# RTD_100R_With_Comp.net
KiCad netlist of a schematic drawn in Altium Designer
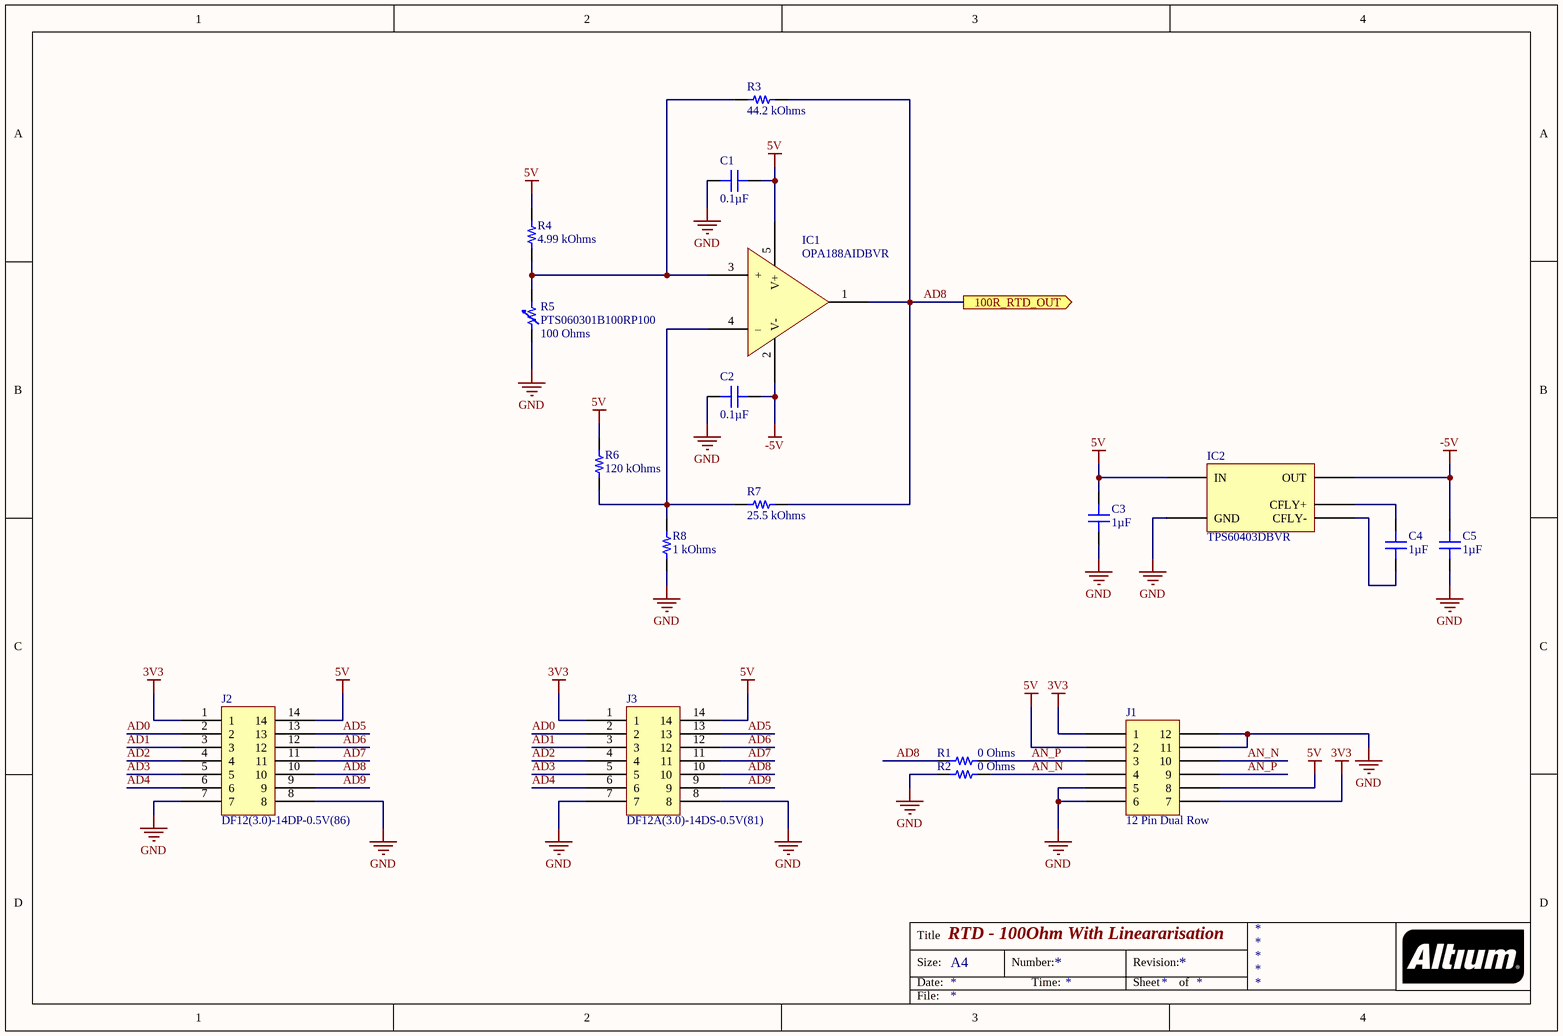
[diagram p0: RTD 100R With Comp.SchDoc]

(export (version "E")
  (design (tool "Eeschema 10.0.6"))
  (components
    (comp (ref "C1")
      (value "0.1µF")
      (footprint "CAP 0603_1608")
      (description "CAP CER 0.1UF 16V Y5V 0603")
      (fields (field (name "PART NUMBER") "CC0603ZRY5V7BB104") (field (name "MANUFACTURER") "Yageo"))
      (libsource (lib "altiumlibrary.com") (part "Capacitor"))
    )
    (comp (ref "C2")
      (value "0.1µF")
      (footprint "CAP 0603_1608")
      (description "CAP CER 0.1UF 16V Y5V 0603")
      (fields (field (name "PART NUMBER") "CC0603ZRY5V7BB104") (field (name "MANUFACTURER") "Yageo"))
      (libsource (lib "altiumlibrary.com") (part "Capacitor"))
    )
    (comp (ref "C3")
      (value "1µF")
      (footprint "CAP 0603_1608")
      (description "CAP CER 1UF 25V X7R 0603")
      (fields
        (field (name "PART NUMBER") "CL10B105KA8NNNC")
        (field (name "MANUFACTURER") "Samsung Electro-Mechanics")
      )
      (libsource (lib "altiumlibrary.com") (part "Capacitor"))
    )
    (comp (ref "C4")
      (value "1µF")
      (footprint "CAP 0603_1608")
      (description "CAP CER 1UF 25V X7R 0603")
      (fields
        (field (name "PART NUMBER") "CL10B105KA8NNNC")
        (field (name "MANUFACTURER") "Samsung Electro-Mechanics")
      )
      (libsource (lib "altiumlibrary.com") (part "Capacitor"))
    )
    (comp (ref "C5")
      (value "1µF")
      (footprint "CAP 0603_1608")
      (description "CAP CER 1UF 25V X7R 0603")
      (fields
        (field (name "PART NUMBER") "CL10B105KA8NNNC")
        (field (name "MANUFACTURER") "Samsung Electro-Mechanics")
      )
      (libsource (lib "altiumlibrary.com") (part "Capacitor"))
    )
    (comp (ref "IC1")
      (value "OPA188AIDBVR")
      (footprint "TI SOT-23-5 DBV")
      (description "IC OPAMP ZER-DRIFT 1CIRC SOT23-5")
      (fields (field (name "MANUFACTURER") "Texas Instruments"))
      (libsource (lib "altiumlibrary.com") (part "TI OPA188 DBV"))
    )
    (comp (ref "IC2")
      (value "TPS60403DBVR")
      (footprint "TI SOT-23-5 DBV")
      (description "IC REG CHARG PUMP INV 60MA SOT23")
      (fields (field (name "MANUFACTURER") "Texas Instruments"))
      (libsource (lib "altiumlibrary.com") (part "TI TPS60403"))
    )
    (comp (ref "J1")
      (value "12 Pin Dual Row")
      (footprint "TE 5650118-3 Card Edge")
      (libsource (lib "CelestialUseful") (part "12 Pin Dual Row"))
    )
    (comp (ref "J2")
      (value "DF12(3.0)-14DP-0.5V(86)")
      (footprint "HIROSE DF12 3.0-14DP-0.5V 86")
      (description "CONN HDR 14POS SMD GOLD")
      (fields (field (name "MANUFACTURER") "Hirose Electric Co Ltd"))
      (libsource (lib "altiumlibrary.com") (part "14 Pin Dual Row"))
    )
    (comp (ref "J3")
      (value "DF12A(3.0)-14DS-0.5V(81)")
      (footprint "HIROSE DF12A 3.0-14DS-0.5V 81")
      (description "CONN RCPT 14POS SMD GOLD")
      (fields (field (name "MANUFACTURER") "Hirose Electric Co Ltd"))
      (libsource (lib "altiumlibrary.com") (part "14 Pin Dual Row"))
    )
    (comp (ref "R1")
      (value "0 Ohms")
      (footprint "RES 0603_1608")
      (description "RES SMD 0 OHM JUMPER 1/10W 0603")
      (fields
        (field (name "PART NUMBER") "ERJ-3GEY0R00V")
        (field (name "MANUFACTURER") "Panasonic Electronic Components")
      )
      (libsource (lib "altiumlibrary.com") (part "Resistor"))
    )
    (comp (ref "R2")
      (value "0 Ohms")
      (footprint "RES 0603_1608")
      (description "RES SMD 0 OHM JUMPER 1/10W 0603")
      (fields
        (field (name "PART NUMBER") "ERJ-3GEY0R00V")
        (field (name "MANUFACTURER") "Panasonic Electronic Components")
      )
      (libsource (lib "altiumlibrary.com") (part "Resistor"))
    )
    (comp (ref "R3")
      (value "44.2 kOhms")
      (footprint "RES 0603_1608")
      (description "RES SMD 44.2K OHM 1% 1/10W 0603")
      (fields
        (field (name "PART NUMBER") "ERJ-3EKF4422V")
        (field (name "MANUFACTURER") "Panasonic Electronic Components")
      )
      (libsource (lib "altiumlibrary.com") (part "Resistor"))
    )
    (comp (ref "R4")
      (value "4.99 kOhms")
      (footprint "RES 0603_1608")
      (description "RES SMD 4.99K OHM 1% 1/10W 0603")
      (fields
        (field (name "PART NUMBER") "ERJ-3EKF4991V")
        (field (name "MANUFACTURER") "Panasonic Electronic Components")
      )
      (libsource (lib "altiumlibrary.com") (part "Resistor"))
    )
    (comp (ref "R5")
      (value "PTS060301B100RP100")
      (footprint "RTD 0603_1608")
      (description "SENSOR RTD 100OHM 1% 0603")
      (fields (field (name "MANUFACTURER") "Vishay Beyschlag") (field (name "RESISTANCE @ 0°C") "100 Ohms"))
      (libsource (lib "altiumlibrary.com") (part "RTD"))
    )
    (comp (ref "R6")
      (value "120 kOhms")
      (footprint "RES 0603_1608")
      (description "RES SMD 120K OHM 1% 1/10W 0603")
      (fields
        (field (name "PART NUMBER") "ERJ-3EKF1203V")
        (field (name "MANUFACTURER") "Panasonic Electronic Components")
      )
      (libsource (lib "altiumlibrary.com") (part "Resistor"))
    )
    (comp (ref "R7")
      (value "25.5 kOhms")
      (footprint "RES 0603_1608")
      (description "RES SMD 25.5K OHM 1% 1/10W 0603")
      (fields
        (field (name "PART NUMBER") "ERJ-3EKF2552V")
        (field (name "MANUFACTURER") "Panasonic Electronic Components")
      )
      (libsource (lib "altiumlibrary.com") (part "Resistor"))
    )
    (comp (ref "R8")
      (value "1 kOhms")
      (footprint "RES 0603_1608")
      (description "RES SMD 1K OHM 1% 1/10W 0603")
      (fields
        (field (name "PART NUMBER") "ERJ-3EKF1001V")
        (field (name "MANUFACTURER") "Panasonic Electronic Components")
      )
      (libsource (lib "altiumlibrary.com") (part "Resistor"))
    )
  )
  (nets
    (net (code "1") (name "-5V") (class "Default")
      (node (ref "C2") (pin "2") (pinfunction "2_2") (pintype "passive"))
      (node (ref "C5") (pin "2") (pinfunction "2_2") (pintype "passive"))
      (node (ref "IC1") (pin "2") (pinfunction "V-_2") (pintype "passive"))
      (node (ref "IC2") (pin "1") (pinfunction "OUT_1") (pintype "passive"))
    )
    (net (code "2") (name "/AD0") (class "Default")
      (node (ref "J2") (pin "2") (pinfunction "2_2") (pintype "passive"))
      (node (ref "J3") (pin "2") (pinfunction "2_2") (pintype "passive"))
    )
    (net (code "3") (name "/AD1") (class "Default")
      (node (ref "J2") (pin "3") (pinfunction "3_3") (pintype "passive"))
      (node (ref "J3") (pin "3") (pinfunction "3_3") (pintype "passive"))
    )
    (net (code "4") (name "/AD2") (class "Default")
      (node (ref "J2") (pin "4") (pinfunction "4_4") (pintype "passive"))
      (node (ref "J3") (pin "4") (pinfunction "4_4") (pintype "passive"))
    )
    (net (code "5") (name "/AD3") (class "Default")
      (node (ref "J2") (pin "5") (pinfunction "5_5") (pintype "passive"))
      (node (ref "J3") (pin "5") (pinfunction "5_5") (pintype "passive"))
    )
    (net (code "6") (name "/AD4") (class "Default")
      (node (ref "J2") (pin "6") (pinfunction "6_6") (pintype "passive"))
      (node (ref "J3") (pin "6") (pinfunction "6_6") (pintype "passive"))
    )
    (net (code "7") (name "/AD5") (class "Default")
      (node (ref "J2") (pin "13") (pinfunction "13_13") (pintype "passive"))
      (node (ref "J3") (pin "13") (pinfunction "13_13") (pintype "passive"))
    )
    (net (code "8") (name "/AD6") (class "Default")
      (node (ref "J2") (pin "12") (pinfunction "12_12") (pintype "passive"))
      (node (ref "J3") (pin "12") (pinfunction "12_12") (pintype "passive"))
    )
    (net (code "9") (name "/AD7") (class "Default")
      (node (ref "J2") (pin "11") (pinfunction "11_11") (pintype "passive"))
      (node (ref "J3") (pin "11") (pinfunction "11_11") (pintype "passive"))
    )
    (net (code "10") (name "/AD8") (class "Default")
      (node (ref "IC1") (pin "1") (pinfunction "OUT_1") (pintype "passive"))
      (node (ref "J2") (pin "10") (pinfunction "10_10") (pintype "passive"))
      (node (ref "J3") (pin "10") (pinfunction "10_10") (pintype "passive"))
      (node (ref "R1") (pin "1") (pinfunction "1_1") (pintype "passive"))
      (node (ref "R3") (pin "2") (pinfunction "2_2") (pintype "passive"))
      (node (ref "R7") (pin "2") (pinfunction "2_2") (pintype "passive"))
    )
    (net (code "11") (name "/AD9") (class "Default")
      (node (ref "J2") (pin "9") (pinfunction "9_9") (pintype "passive"))
      (node (ref "J3") (pin "9") (pinfunction "9_9") (pintype "passive"))
    )
    (net (code "12") (name "/AN_N") (class "Default")
      (node (ref "J1") (pin "10") (pinfunction "10_10") (pintype "passive"))
      (node (ref "J1") (pin "4") (pinfunction "4_4") (pintype "passive"))
      (node (ref "R2") (pin "2") (pinfunction "2_2") (pintype "passive"))
    )
    (net (code "13") (name "/AN_P") (class "Default")
      (node (ref "J1") (pin "3") (pinfunction "3_3") (pintype "passive"))
      (node (ref "J1") (pin "9") (pinfunction "9_9") (pintype "passive"))
      (node (ref "R1") (pin "2") (pinfunction "2_2") (pintype "passive"))
    )
    (net (code "14") (name "3V3") (class "Default")
      (node (ref "J1") (pin "1") (pinfunction "1_1") (pintype "passive"))
      (node (ref "J1") (pin "7") (pinfunction "7_7") (pintype "passive"))
      (node (ref "J2") (pin "1") (pinfunction "1_1") (pintype "passive"))
      (node (ref "J3") (pin "1") (pinfunction "1_1") (pintype "passive"))
    )
    (net (code "15") (name "5V") (class "Default")
      (node (ref "C1") (pin "2") (pinfunction "2_2") (pintype "passive"))
      (node (ref "C3") (pin "2") (pinfunction "2_2") (pintype "passive"))
      (node (ref "IC1") (pin "5") (pinfunction "V+_5") (pintype "passive"))
      (node (ref "IC2") (pin "2") (pinfunction "IN_2") (pintype "passive"))
      (node (ref "J1") (pin "2") (pinfunction "2_2") (pintype "passive"))
      (node (ref "J1") (pin "8") (pinfunction "8_8") (pintype "passive"))
      (node (ref "J2") (pin "14") (pinfunction "14_14") (pintype "passive"))
      (node (ref "J3") (pin "14") (pinfunction "14_14") (pintype "passive"))
      (node (ref "R4") (pin "2") (pinfunction "2_2") (pintype "passive"))
      (node (ref "R6") (pin "2") (pinfunction "2_2") (pintype "passive"))
    )
    (net (code "16") (name "GND") (class "Default")
      (node (ref "C1") (pin "1") (pinfunction "1_1") (pintype "passive"))
      (node (ref "C2") (pin "1") (pinfunction "1_1") (pintype "passive"))
      (node (ref "C3") (pin "1") (pinfunction "1_1") (pintype "passive"))
      (node (ref "C5") (pin "1") (pinfunction "1_1") (pintype "passive"))
      (node (ref "IC2") (pin "4") (pinfunction "GND_4") (pintype "passive"))
      (node (ref "J1") (pin "11") (pinfunction "11_11") (pintype "passive"))
      (node (ref "J1") (pin "12") (pinfunction "12_12") (pintype "passive"))
      (node (ref "J1") (pin "5") (pinfunction "5_5") (pintype "passive"))
      (node (ref "J1") (pin "6") (pinfunction "6_6") (pintype "passive"))
      (node (ref "J2") (pin "7") (pinfunction "7_7") (pintype "passive"))
      (node (ref "J2") (pin "8") (pinfunction "8_8") (pintype "passive"))
      (node (ref "J3") (pin "7") (pinfunction "7_7") (pintype "passive"))
      (node (ref "J3") (pin "8") (pinfunction "8_8") (pintype "passive"))
      (node (ref "R2") (pin "1") (pinfunction "1_1") (pintype "passive"))
      (node (ref "R5") (pin "1") (pinfunction "1_1") (pintype "passive"))
      (node (ref "R8") (pin "1") (pinfunction "1_1") (pintype "passive"))
    )
    (net (code "17") (name "Net-(IC1-+)") (class "Default")
      (node (ref "IC1") (pin "3") (pinfunction "+_3") (pintype "passive"))
      (node (ref "R3") (pin "1") (pinfunction "1_1") (pintype "passive"))
      (node (ref "R4") (pin "1") (pinfunction "1_1") (pintype "passive"))
      (node (ref "R5") (pin "2") (pinfunction "2_2") (pintype "passive"))
    )
    (net (code "18") (name "Net-(IC1-–)") (class "Default")
      (node (ref "IC1") (pin "4") (pinfunction "–_4") (pintype "passive"))
      (node (ref "R6") (pin "1") (pinfunction "1_1") (pintype "passive"))
      (node (ref "R7") (pin "1") (pinfunction "1_1") (pintype "passive"))
      (node (ref "R8") (pin "2") (pinfunction "2_2") (pintype "passive"))
    )
    (net (code "19") (name "Net-(IC2-CFLY+)") (class "Default")
      (node (ref "C4") (pin "2") (pinfunction "2_2") (pintype "passive"))
      (node (ref "IC2") (pin "5") (pinfunction "CFLY+_5") (pintype "passive"))
    )
    (net (code "20") (name "Net-(IC2-CFLY-)") (class "Default")
      (node (ref "C4") (pin "1") (pinfunction "1_1") (pintype "passive"))
      (node (ref "IC2") (pin "3") (pinfunction "CFLY-_3") (pintype "passive"))
    )
  )
)
